# EL_Driver.net
KiCad netlist of a schematic drawn in EAGLE
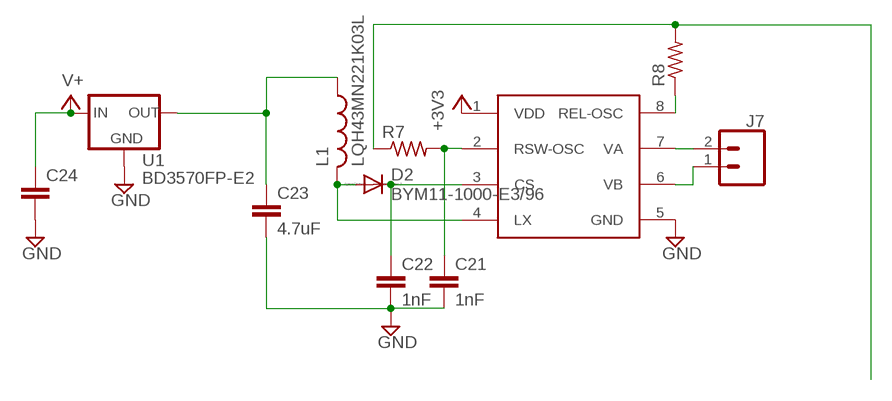
[diagram p0: schematic, sheet 1]

(export (version "E")
  (design (tool "Eeschema 10.0.6"))
  (components
    (comp (ref "C21")
      (value "1nF")
      (footprint "eagle-import:C1206")
      (libsource (lib "eagle-import") (part "C-EUC1206"))
    )
    (comp (ref "C22")
      (value "1nF")
      (footprint "eagle-import:C1206")
      (libsource (lib "eagle-import") (part "C-EUC1206"))
    )
    (comp (ref "C23")
      (value "4.7uF")
      (footprint "eagle-import:C1206")
      (libsource (lib "eagle-import") (part "C-EUC1206"))
    )
    (comp (ref "C24")
      (value "C-EUC1206")
      (footprint "eagle-import:C1206")
      (libsource (lib "eagle-import") (part "C-EUC1206"))
    )
    (comp (ref "D2")
      (value "BYM11-1000-E3/96")
      (footprint "eagle-import:MELF-MLL41")
      (libsource (lib "eagle-import") (part "DIODE-MELF-MLL41"))
    )
    (comp (ref "J7")
      (value "CONN_02")
      (footprint "eagle-import:1X02")
      (libsource (lib "eagle-import") (part "CONN_02"))
    )
    (comp (ref "L1")
      (value "LQH43MN221K03L")
      (footprint "eagle-import:L1812")
      (libsource (lib "eagle-import") (part "L-USL1812"))
    )
    (comp (ref "R7")
      (value "R-US_R1206")
      (footprint "eagle-import:R1206")
      (libsource (lib "eagle-import") (part "R-US_R1206"))
    )
    (comp (ref "R8")
      (value "R-US_R1206")
      (footprint "eagle-import:R1206")
      (libsource (lib "eagle-import") (part "R-US_R1206"))
    )
    (comp (ref "U$3")
      (value "HV830")
      (footprint "eagle-import:SOIC8")
      (libsource (lib "eagle-import") (part "HV830"))
    )
    (comp (ref "U1")
      (value "BD3570FP-E2")
      (footprint "eagle-import:TO-252")
      (libsource (lib "eagle-import") (part "V_REG_78XX7812"))
    )
  )
  (nets
    (net (code "1") (name "+3V3") (class "Default")
      (node (ref "U$3") (pin "1") (pinfunction "VDD_1") (pintype "bidirectional"))
    )
    (net (code "2") (name "GND") (class "Default")
      (node (ref "C21") (pin "2") (pinfunction "2_2") (pintype "passive"))
      (node (ref "C22") (pin "2") (pinfunction "2_2") (pintype "passive"))
      (node (ref "C23") (pin "2") (pinfunction "2_2") (pintype "passive"))
      (node (ref "C24") (pin "2") (pinfunction "2_2") (pintype "passive"))
      (node (ref "U$3") (pin "5") (pinfunction "GND_5") (pintype "bidirectional"))
      (node (ref "U1") (pin "3") (pinfunction "GND_3") (pintype "input"))
    )
    (net (code "3") (name "Net-(R7-Pad1)") (class "Default")
      (node (ref "R7") (pin "1") (pinfunction "1_1") (pintype "passive"))
      (node (ref "R8") (pin "2") (pinfunction "2_2") (pintype "passive"))
    )
    (net (code "4") (name "Net-(U$3-CS)") (class "Default")
      (node (ref "C22") (pin "1") (pinfunction "1_1") (pintype "passive"))
      (node (ref "D2") (pin "C") (pinfunction "C_C") (pintype "passive"))
      (node (ref "U$3") (pin "3") (pinfunction "CS_3") (pintype "bidirectional"))
    )
    (net (code "5") (name "Net-(U$3-LX)") (class "Default")
      (node (ref "D2") (pin "A") (pinfunction "A_A") (pintype "passive"))
      (node (ref "L1") (pin "2") (pinfunction "2_2") (pintype "passive"))
      (node (ref "U$3") (pin "4") (pinfunction "LX_4") (pintype "bidirectional"))
    )
    (net (code "6") (name "Net-(U$3-REL-OSC)") (class "Default")
      (node (ref "R8") (pin "1") (pinfunction "1_1") (pintype "passive"))
      (node (ref "U$3") (pin "8") (pinfunction "REL-OSC_8") (pintype "bidirectional"))
    )
    (net (code "7") (name "Net-(U$3-RSW-OSC)") (class "Default")
      (node (ref "C21") (pin "1") (pinfunction "1_1") (pintype "passive"))
      (node (ref "R7") (pin "2") (pinfunction "2_2") (pintype "passive"))
      (node (ref "U$3") (pin "2") (pinfunction "RSW-OSC_2") (pintype "bidirectional"))
    )
    (net (code "8") (name "Net-(U$3-VA)") (class "Default")
      (node (ref "J7") (pin "2") (pinfunction "2_2") (pintype "passive"))
      (node (ref "U$3") (pin "7") (pinfunction "VA_7") (pintype "bidirectional"))
    )
    (net (code "9") (name "Net-(U$3-VB)") (class "Default")
      (node (ref "J7") (pin "1") (pinfunction "1_1") (pintype "passive"))
      (node (ref "U$3") (pin "6") (pinfunction "VB_6") (pintype "bidirectional"))
    )
    (net (code "10") (name "Net-(U1-OUT)") (class "Default")
      (node (ref "C23") (pin "1") (pinfunction "1_1") (pintype "passive"))
      (node (ref "L1") (pin "1") (pinfunction "1_1") (pintype "passive"))
      (node (ref "U1") (pin "2") (pinfunction "OUT_2") (pintype "passive"))
    )
    (net (code "11") (name "V+") (class "Default")
      (node (ref "C24") (pin "1") (pinfunction "1_1") (pintype "passive"))
      (node (ref "U1") (pin "1") (pinfunction "IN_1") (pintype "input"))
    )
  )
)
